# Teensy_board.net
KiCad netlist of a schematic drawn in EAGLE
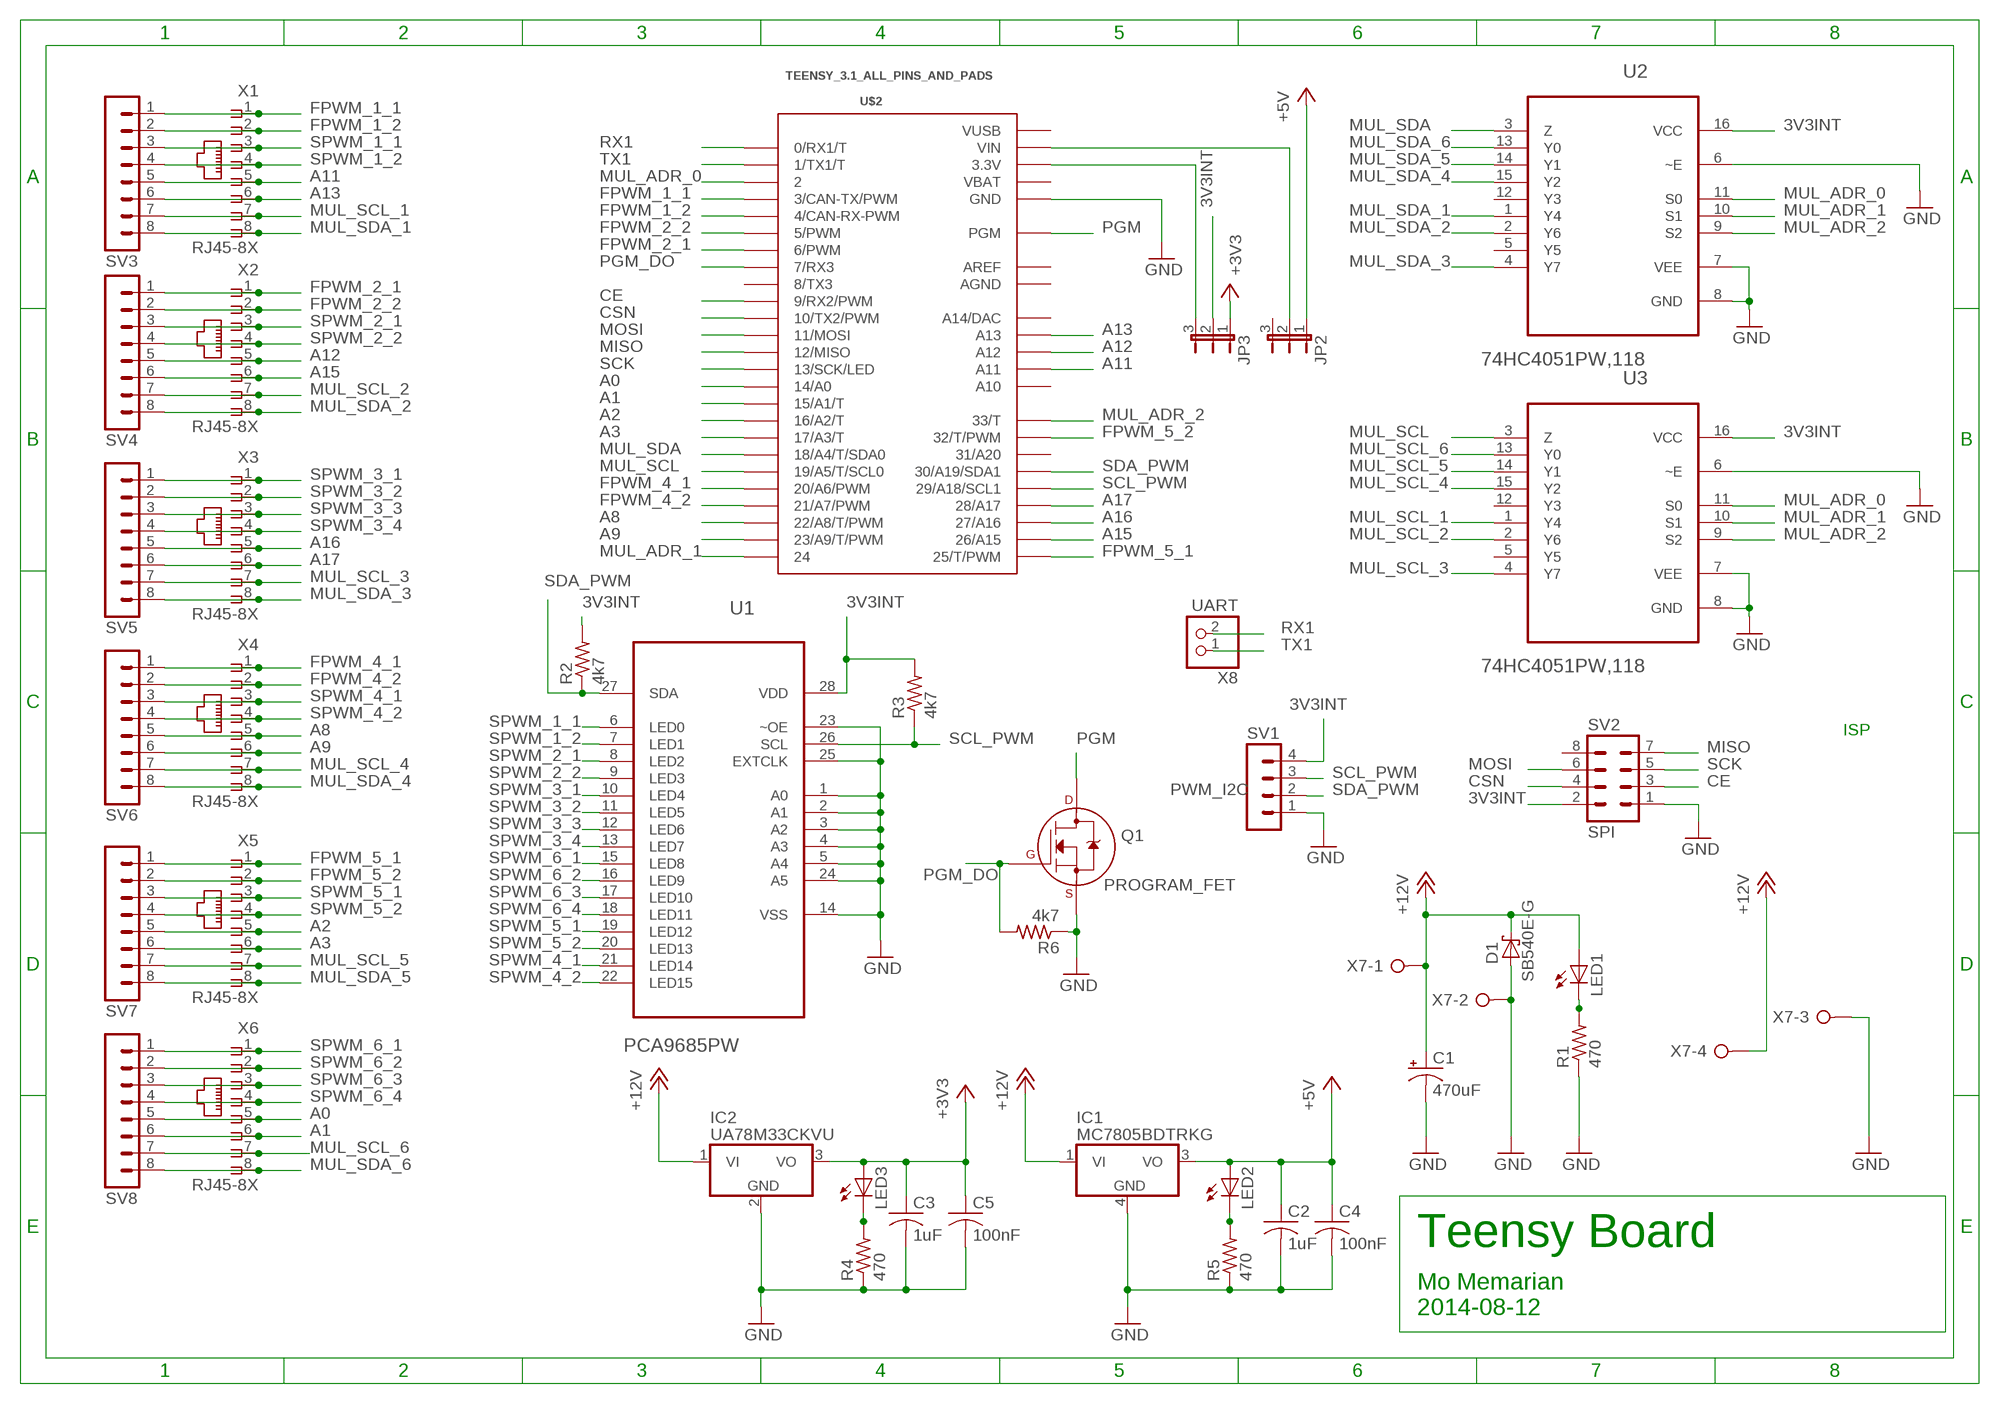
[diagram p0: schematic, sheet 1]

(export (version "E")
  (design (tool "Eeschema 10.0.6"))
  (components
    (comp (ref "C1")
      (value "470uF")
      (footprint "eagle-import:E5-10,5")
      (libsource (lib "eagle-import") (part "CPOL-USE5-10.5"))
    )
    (comp (ref "C2")
      (value "1uF")
      (footprint "eagle-import:C0603")
      (libsource (lib "eagle-import") (part "C-USC0603"))
    )
    (comp (ref "C3")
      (value "1uF")
      (footprint "eagle-import:C0603")
      (libsource (lib "eagle-import") (part "C-USC0603"))
    )
    (comp (ref "C4")
      (value "100nF")
      (footprint "eagle-import:C0603")
      (libsource (lib "eagle-import") (part "C-USC0603"))
    )
    (comp (ref "C5")
      (value "100nF")
      (footprint "eagle-import:C0603")
      (libsource (lib "eagle-import") (part "C-USC0603"))
    )
    (comp (ref "D1")
      (value "SB540E-G")
      (footprint "eagle-import:DO201T15")
      (libsource (lib "eagle-import") (part "SB540E-G"))
    )
    (comp (ref "IC1")
      (value "MC7805BDTRKG")
      (footprint "eagle-import:DPACK_3")
      (libsource (lib "eagle-import") (part "MC7805BDTRKG"))
    )
    (comp (ref "IC2")
      (value "UA78M33CKVU")
      (footprint "eagle-import:DPACK")
      (libsource (lib "eagle-import") (part "UA78MKVU33C"))
    )
    (comp (ref "JP2")
      (value "JP2E")
      (footprint "eagle-import:JP2")
      (libsource (lib "eagle-import") (part "JP2E"))
    )
    (comp (ref "JP3")
      (value "JP2E")
      (footprint "eagle-import:JP2")
      (libsource (lib "eagle-import") (part "JP2E"))
    )
    (comp (ref "LED1")
      (value "LEDSML1206")
      (footprint "eagle-import:SML1206")
      (libsource (lib "eagle-import") (part "LEDSML1206"))
    )
    (comp (ref "LED2")
      (value "LEDSML1206")
      (footprint "eagle-import:SML1206")
      (libsource (lib "eagle-import") (part "LEDSML1206"))
    )
    (comp (ref "LED3")
      (value "LEDSML1206")
      (footprint "eagle-import:SML1206")
      (libsource (lib "eagle-import") (part "LEDSML1206"))
    )
    (comp (ref "Q1")
      (value "PROGRAM_FET")
      (footprint "eagle-import:SOT-23")
      (libsource (lib "eagle-import") (part "2N700_SOT232"))
    )
    (comp (ref "R1")
      (value "470")
      (footprint "eagle-import:R0603")
      (libsource (lib "eagle-import") (part "R-US_R0603"))
    )
    (comp (ref "R2")
      (value "4k7")
      (footprint "eagle-import:R0603")
      (libsource (lib "eagle-import") (part "R-US_R0603"))
    )
    (comp (ref "R3")
      (value "4k7")
      (footprint "eagle-import:R0603")
      (libsource (lib "eagle-import") (part "R-US_R0603"))
    )
    (comp (ref "R4")
      (value "470")
      (footprint "eagle-import:R0603")
      (libsource (lib "eagle-import") (part "R-US_R0603"))
    )
    (comp (ref "R5")
      (value "470")
      (footprint "eagle-import:R0603")
      (libsource (lib "eagle-import") (part "R-US_R0603"))
    )
    (comp (ref "R6")
      (value "4k7")
      (footprint "eagle-import:R0603")
      (libsource (lib "eagle-import") (part "R-US_R0603"))
    )
    (comp (ref "SV1")
      (value "PWM_I2C")
      (footprint "eagle-import:MA04-1")
      (libsource (lib "eagle-import") (part "MA04-1"))
    )
    (comp (ref "SV2")
      (value "SPI")
      (footprint "eagle-import:MA04-2")
      (libsource (lib "eagle-import") (part "MA04-2"))
    )
    (comp (ref "SV3")
      (value "MA08-1")
      (footprint "eagle-import:MA08-1")
      (libsource (lib "eagle-import") (part "MA08-1"))
    )
    (comp (ref "SV4")
      (value "MA08-1")
      (footprint "eagle-import:MA08-1")
      (libsource (lib "eagle-import") (part "MA08-1"))
    )
    (comp (ref "SV5")
      (value "MA08-1")
      (footprint "eagle-import:MA08-1")
      (libsource (lib "eagle-import") (part "MA08-1"))
    )
    (comp (ref "SV6")
      (value "MA08-1")
      (footprint "eagle-import:MA08-1")
      (libsource (lib "eagle-import") (part "MA08-1"))
    )
    (comp (ref "SV7")
      (value "MA08-1")
      (footprint "eagle-import:MA08-1")
      (libsource (lib "eagle-import") (part "MA08-1"))
    )
    (comp (ref "SV8")
      (value "MA08-1")
      (footprint "eagle-import:MA08-1")
      (libsource (lib "eagle-import") (part "MA08-1"))
    )
    (comp (ref "U$2")
      (value "TEENSY_3.1_ALL_PINS_AND_PADS")
      (footprint "eagle-import:TEENSY_3.1_ALLPINS")
      (libsource (lib "eagle-import") (part "TEENSY_3.1_ALL_PINS_AND_PADS"))
    )
    (comp (ref "U1")
      (value "PCA9685PW")
      (footprint "eagle-import:SOP65P640X110-28N")
      (libsource (lib "eagle-import") (part "PCA9685PW"))
    )
    (comp (ref "U2")
      (value "74HC4051PW,118")
      (footprint "eagle-import:SOP65P640X110-16N")
      (libsource (lib "eagle-import") (part "74HC4051PW,118"))
    )
    (comp (ref "U3")
      (value "74HC4051PW,118")
      (footprint "eagle-import:SOP65P640X110-16N")
      (libsource (lib "eagle-import") (part "74HC4051PW,118"))
    )
    (comp (ref "X1")
      (value "RJ45-8X")
      (footprint "eagle-import:RJ45-NO-SHIELD")
      (libsource (lib "eagle-import") (part "RJ45-8X"))
    )
    (comp (ref "X2")
      (value "RJ45-8X")
      (footprint "eagle-import:RJ45-NO-SHIELD")
      (libsource (lib "eagle-import") (part "RJ45-8X"))
    )
    (comp (ref "X3")
      (value "RJ45-8X")
      (footprint "eagle-import:RJ45-NO-SHIELD")
      (libsource (lib "eagle-import") (part "RJ45-8X"))
    )
    (comp (ref "X4")
      (value "RJ45-8X")
      (footprint "eagle-import:RJ45-NO-SHIELD")
      (libsource (lib "eagle-import") (part "RJ45-8X"))
    )
    (comp (ref "X5")
      (value "RJ45-8X")
      (footprint "eagle-import:RJ45-NO-SHIELD")
      (libsource (lib "eagle-import") (part "RJ45-8X"))
    )
    (comp (ref "X6")
      (value "RJ45-8X")
      (footprint "eagle-import:RJ45-NO-SHIELD")
      (libsource (lib "eagle-import") (part "RJ45-8X"))
    )
    (comp (ref "X7")
      (value "W237-04P")
      (footprint "eagle-import:W237-4P")
      (libsource (lib "eagle-import") (part "W237-04P"))
    )
    (comp (ref "X8")
      (value "UART")
      (footprint "eagle-import:1X02")
      (libsource (lib "eagle-import") (part "PINHD-1X2"))
    )
  )
  (nets
    (net (code "1") (name "+3V3") (class "Default")
      (node (ref "C3") (pin "1") (pinfunction "1_1") (pintype "passive"))
      (node (ref "C5") (pin "1") (pinfunction "1_1") (pintype "passive"))
      (node (ref "IC2") (pin "3") (pinfunction "VO_3") (pintype "passive"))
      (node (ref "JP3") (pin "1") (pinfunction "1_1") (pintype "passive"))
      (node (ref "LED3") (pin "A") (pinfunction "A_A") (pintype "passive"))
    )
    (net (code "2") (name "+5V") (class "Default")
      (node (ref "C2") (pin "1") (pinfunction "1_1") (pintype "passive"))
      (node (ref "C4") (pin "1") (pinfunction "1_1") (pintype "passive"))
      (node (ref "IC1") (pin "3") (pinfunction "VO_3") (pintype "passive"))
      (node (ref "JP2") (pin "1") (pinfunction "1_1") (pintype "passive"))
      (node (ref "LED2") (pin "A") (pinfunction "A_A") (pintype "passive"))
    )
    (net (code "3") (name "+12V") (class "Default")
      (node (ref "C1") (pin "+") (pinfunction "+_+") (pintype "passive"))
      (node (ref "D1") (pin "C") (pinfunction "C_C") (pintype "passive"))
      (node (ref "IC1") (pin "1") (pinfunction "VI_1") (pintype "input"))
      (node (ref "IC2") (pin "1") (pinfunction "VI_1") (pintype "input"))
      (node (ref "LED1") (pin "A") (pinfunction "A_A") (pintype "passive"))
      (node (ref "X7") (pin "1") (pinfunction "KL_1") (pintype "passive"))
      (node (ref "X7") (pin "4") (pinfunction "KL_4") (pintype "passive"))
    )
    (net (code "4") (name "/3V3INT") (class "Default")
      (node (ref "JP3") (pin "2") (pinfunction "2_2") (pintype "passive"))
      (node (ref "R2") (pin "2") (pinfunction "2_2") (pintype "passive"))
      (node (ref "R3") (pin "2") (pinfunction "2_2") (pintype "passive"))
      (node (ref "SV1") (pin "4") (pinfunction "4_4") (pintype "passive"))
      (node (ref "SV2") (pin "2") (pinfunction "2_2") (pintype "passive"))
      (node (ref "U1") (pin "28") (pinfunction "VDD_28") (pintype "power_in"))
      (node (ref "U2") (pin "16") (pinfunction "VCC_16") (pintype "power_in"))
      (node (ref "U3") (pin "16") (pinfunction "VCC_16") (pintype "power_in"))
    )
    (net (code "5") (name "/A0") (class "Default")
      (node (ref "SV8") (pin "5") (pinfunction "5_5") (pintype "passive"))
      (node (ref "U$2") (pin "14/A0") (pinfunction "14/A0_14/A0") (pintype "bidirectional"))
      (node (ref "X6") (pin "5") (pinfunction "5_5") (pintype "passive"))
    )
    (net (code "6") (name "/A1") (class "Default")
      (node (ref "SV8") (pin "6") (pinfunction "6_6") (pintype "passive"))
      (node (ref "U$2") (pin "15/A1") (pinfunction "15/A1/T_15/A1") (pintype "bidirectional"))
      (node (ref "X6") (pin "6") (pinfunction "6_6") (pintype "passive"))
    )
    (net (code "7") (name "/A2") (class "Default")
      (node (ref "SV7") (pin "5") (pinfunction "5_5") (pintype "passive"))
      (node (ref "U$2") (pin "16/A2") (pinfunction "16/A2/T_16/A2") (pintype "bidirectional"))
      (node (ref "X5") (pin "5") (pinfunction "5_5") (pintype "passive"))
    )
    (net (code "8") (name "/A3") (class "Default")
      (node (ref "SV7") (pin "6") (pinfunction "6_6") (pintype "passive"))
      (node (ref "U$2") (pin "17/A3") (pinfunction "17/A3/T_17/A3") (pintype "bidirectional"))
      (node (ref "X5") (pin "6") (pinfunction "6_6") (pintype "passive"))
    )
    (net (code "9") (name "/A8") (class "Default")
      (node (ref "SV6") (pin "5") (pinfunction "5_5") (pintype "passive"))
      (node (ref "U$2") (pin "22/A8") (pinfunction "22/A8/T/PWM_22/A8") (pintype "bidirectional"))
      (node (ref "X4") (pin "5") (pinfunction "5_5") (pintype "passive"))
    )
    (net (code "10") (name "/A9") (class "Default")
      (node (ref "SV6") (pin "6") (pinfunction "6_6") (pintype "passive"))
      (node (ref "U$2") (pin "23/A9") (pinfunction "23/A9/T/PWM_23/A9") (pintype "bidirectional"))
      (node (ref "X4") (pin "6") (pinfunction "6_6") (pintype "passive"))
    )
    (net (code "11") (name "/A11") (class "Default")
      (node (ref "SV3") (pin "5") (pinfunction "5_5") (pintype "passive"))
      (node (ref "U$2") (pin "A11") (pinfunction "A11_A11") (pintype "bidirectional"))
      (node (ref "X1") (pin "5") (pinfunction "5_5") (pintype "passive"))
    )
    (net (code "12") (name "/A12") (class "Default")
      (node (ref "SV4") (pin "5") (pinfunction "5_5") (pintype "passive"))
      (node (ref "U$2") (pin "A12") (pinfunction "A12_A12") (pintype "bidirectional"))
      (node (ref "X2") (pin "5") (pinfunction "5_5") (pintype "passive"))
    )
    (net (code "13") (name "/A13") (class "Default")
      (node (ref "SV3") (pin "6") (pinfunction "6_6") (pintype "passive"))
      (node (ref "U$2") (pin "A13") (pinfunction "A13_A13") (pintype "bidirectional"))
      (node (ref "X1") (pin "6") (pinfunction "6_6") (pintype "passive"))
    )
    (net (code "14") (name "/A15") (class "Default")
      (node (ref "SV4") (pin "6") (pinfunction "6_6") (pintype "passive"))
      (node (ref "U$2") (pin "26") (pinfunction "26/A15_26") (pintype "bidirectional"))
      (node (ref "X2") (pin "6") (pinfunction "6_6") (pintype "passive"))
    )
    (net (code "15") (name "/A16") (class "Default")
      (node (ref "SV5") (pin "5") (pinfunction "5_5") (pintype "passive"))
      (node (ref "U$2") (pin "27") (pinfunction "27/A16_27") (pintype "bidirectional"))
      (node (ref "X3") (pin "5") (pinfunction "5_5") (pintype "passive"))
    )
    (net (code "16") (name "/A17") (class "Default")
      (node (ref "SV5") (pin "6") (pinfunction "6_6") (pintype "passive"))
      (node (ref "U$2") (pin "28") (pinfunction "28/A17_28") (pintype "bidirectional"))
      (node (ref "X3") (pin "6") (pinfunction "6_6") (pintype "passive"))
    )
    (net (code "17") (name "/AGND") (class "Default")
      (node (ref "U$2") (pin "AGND") (pinfunction "AGND_AGND") (pintype "power_in"))
    )
    (net (code "18") (name "/AREF") (class "Default")
      (node (ref "U$2") (pin "AREF") (pinfunction "AREF_AREF") (pintype "power_in"))
    )
    (net (code "19") (name "/CE") (class "Default")
      (node (ref "SV2") (pin "3") (pinfunction "3_3") (pintype "passive"))
      (node (ref "U$2") (pin "9") (pinfunction "9/RX2/PWM_9") (pintype "bidirectional"))
    )
    (net (code "20") (name "/CSN") (class "Default")
      (node (ref "SV2") (pin "4") (pinfunction "4_4") (pintype "passive"))
      (node (ref "U$2") (pin "10") (pinfunction "10/TX2/PWM_10") (pintype "bidirectional"))
    )
    (net (code "21") (name "/FPWM_1_1") (class "Default")
      (node (ref "SV3") (pin "1") (pinfunction "1_1") (pintype "passive"))
      (node (ref "U$2") (pin "3") (pinfunction "3/CAN-TX/PWM_3") (pintype "bidirectional"))
      (node (ref "X1") (pin "1") (pinfunction "1_1") (pintype "passive"))
    )
    (net (code "22") (name "/FPWM_1_2") (class "Default")
      (node (ref "SV3") (pin "2") (pinfunction "2_2") (pintype "passive"))
      (node (ref "U$2") (pin "4") (pinfunction "4/CAN-RX-PWM_4") (pintype "bidirectional"))
      (node (ref "X1") (pin "2") (pinfunction "2_2") (pintype "passive"))
    )
    (net (code "23") (name "/FPWM_2_1") (class "Default")
      (node (ref "SV4") (pin "1") (pinfunction "1_1") (pintype "passive"))
      (node (ref "U$2") (pin "6") (pinfunction "6/PWM_6") (pintype "bidirectional"))
      (node (ref "X2") (pin "1") (pinfunction "1_1") (pintype "passive"))
    )
    (net (code "24") (name "/FPWM_2_2") (class "Default")
      (node (ref "SV4") (pin "2") (pinfunction "2_2") (pintype "passive"))
      (node (ref "U$2") (pin "5") (pinfunction "5/PWM_5") (pintype "bidirectional"))
      (node (ref "X2") (pin "2") (pinfunction "2_2") (pintype "passive"))
    )
    (net (code "25") (name "/FPWM_4_1") (class "Default")
      (node (ref "SV6") (pin "1") (pinfunction "1_1") (pintype "passive"))
      (node (ref "U$2") (pin "20/A6") (pinfunction "20/A6/PWM_20/A6") (pintype "bidirectional"))
      (node (ref "X4") (pin "1") (pinfunction "1_1") (pintype "passive"))
    )
    (net (code "26") (name "/FPWM_4_2") (class "Default")
      (node (ref "SV6") (pin "2") (pinfunction "2_2") (pintype "passive"))
      (node (ref "U$2") (pin "21/A7") (pinfunction "21/A7/PWM_21/A7") (pintype "bidirectional"))
      (node (ref "X4") (pin "2") (pinfunction "2_2") (pintype "passive"))
    )
    (net (code "27") (name "/FPWM_5_1") (class "Default")
      (node (ref "SV7") (pin "1") (pinfunction "1_1") (pintype "passive"))
      (node (ref "U$2") (pin "25") (pinfunction "25/T/PWM_25") (pintype "bidirectional"))
      (node (ref "X5") (pin "1") (pinfunction "1_1") (pintype "passive"))
    )
    (net (code "28") (name "/FPWM_5_2") (class "Default")
      (node (ref "SV7") (pin "2") (pinfunction "2_2") (pintype "passive"))
      (node (ref "U$2") (pin "32") (pinfunction "32/T/PWM_32") (pintype "bidirectional"))
      (node (ref "X5") (pin "2") (pinfunction "2_2") (pintype "passive"))
    )
    (net (code "29") (name "/MISO") (class "Default")
      (node (ref "SV2") (pin "7") (pinfunction "7_7") (pintype "passive"))
      (node (ref "U$2") (pin "12") (pinfunction "12/MISO_12") (pintype "bidirectional"))
    )
    (net (code "30") (name "/MOSI") (class "Default")
      (node (ref "SV2") (pin "6") (pinfunction "6_6") (pintype "passive"))
      (node (ref "U$2") (pin "11") (pinfunction "11/MOSI_11") (pintype "bidirectional"))
    )
    (net (code "31") (name "/MUL_ADR_0") (class "Default")
      (node (ref "U$2") (pin "2") (pinfunction "2_2") (pintype "bidirectional"))
      (node (ref "U2") (pin "11") (pinfunction "S0_11") (pintype "input"))
      (node (ref "U3") (pin "11") (pinfunction "S0_11") (pintype "input"))
    )
    (net (code "32") (name "/MUL_ADR_1") (class "Default")
      (node (ref "U$2") (pin "24") (pinfunction "24_24") (pintype "bidirectional"))
      (node (ref "U2") (pin "10") (pinfunction "S1_10") (pintype "input"))
      (node (ref "U3") (pin "10") (pinfunction "S1_10") (pintype "input"))
    )
    (net (code "33") (name "/MUL_ADR_2") (class "Default")
      (node (ref "U$2") (pin "33") (pinfunction "33/T_33") (pintype "bidirectional"))
      (node (ref "U2") (pin "9") (pinfunction "S2_9") (pintype "input"))
      (node (ref "U3") (pin "9") (pinfunction "S2_9") (pintype "input"))
    )
    (net (code "34") (name "/MUL_SCL") (class "Default")
      (node (ref "U$2") (pin "19/A5") (pinfunction "19/A5/T/SCL0_19/A5") (pintype "bidirectional"))
      (node (ref "U3") (pin "3") (pinfunction "Z_3") (pintype "bidirectional"))
    )
    (net (code "35") (name "/MUL_SCL_1") (class "Default")
      (node (ref "SV3") (pin "7") (pinfunction "7_7") (pintype "passive"))
      (node (ref "U3") (pin "1") (pinfunction "Y4_1") (pintype "bidirectional"))
      (node (ref "X1") (pin "7") (pinfunction "7_7") (pintype "passive"))
    )
    (net (code "36") (name "/MUL_SCL_2") (class "Default")
      (node (ref "SV4") (pin "7") (pinfunction "7_7") (pintype "passive"))
      (node (ref "U3") (pin "2") (pinfunction "Y6_2") (pintype "bidirectional"))
      (node (ref "X2") (pin "7") (pinfunction "7_7") (pintype "passive"))
    )
    (net (code "37") (name "/MUL_SCL_3") (class "Default")
      (node (ref "SV5") (pin "7") (pinfunction "7_7") (pintype "passive"))
      (node (ref "U3") (pin "4") (pinfunction "Y7_4") (pintype "bidirectional"))
      (node (ref "X3") (pin "7") (pinfunction "7_7") (pintype "passive"))
    )
    (net (code "38") (name "/MUL_SCL_4") (class "Default")
      (node (ref "SV6") (pin "7") (pinfunction "7_7") (pintype "passive"))
      (node (ref "U3") (pin "15") (pinfunction "Y2_15") (pintype "bidirectional"))
      (node (ref "X4") (pin "7") (pinfunction "7_7") (pintype "passive"))
    )
    (net (code "39") (name "/MUL_SCL_5") (class "Default")
      (node (ref "SV7") (pin "7") (pinfunction "7_7") (pintype "passive"))
      (node (ref "U3") (pin "14") (pinfunction "Y1_14") (pintype "bidirectional"))
      (node (ref "X5") (pin "7") (pinfunction "7_7") (pintype "passive"))
    )
    (net (code "40") (name "/MUL_SCL_6") (class "Default")
      (node (ref "SV8") (pin "7") (pinfunction "7_7") (pintype "passive"))
      (node (ref "U3") (pin "13") (pinfunction "Y0_13") (pintype "bidirectional"))
      (node (ref "X6") (pin "7") (pinfunction "7_7") (pintype "passive"))
    )
    (net (code "41") (name "/MUL_SDA") (class "Default")
      (node (ref "U$2") (pin "18/A4") (pinfunction "18/A4/T/SDA0_18/A4") (pintype "bidirectional"))
      (node (ref "U2") (pin "3") (pinfunction "Z_3") (pintype "bidirectional"))
    )
    (net (code "42") (name "/MUL_SDA_1") (class "Default")
      (node (ref "SV3") (pin "8") (pinfunction "8_8") (pintype "passive"))
      (node (ref "U2") (pin "1") (pinfunction "Y4_1") (pintype "bidirectional"))
      (node (ref "X1") (pin "8") (pinfunction "8_8") (pintype "passive"))
    )
    (net (code "43") (name "/MUL_SDA_2") (class "Default")
      (node (ref "SV4") (pin "8") (pinfunction "8_8") (pintype "passive"))
      (node (ref "U2") (pin "2") (pinfunction "Y6_2") (pintype "bidirectional"))
      (node (ref "X2") (pin "8") (pinfunction "8_8") (pintype "passive"))
    )
    (net (code "44") (name "/MUL_SDA_3") (class "Default")
      (node (ref "SV5") (pin "8") (pinfunction "8_8") (pintype "passive"))
      (node (ref "U2") (pin "4") (pinfunction "Y7_4") (pintype "bidirectional"))
      (node (ref "X3") (pin "8") (pinfunction "8_8") (pintype "passive"))
    )
    (net (code "45") (name "/MUL_SDA_4") (class "Default")
      (node (ref "SV6") (pin "8") (pinfunction "8_8") (pintype "passive"))
      (node (ref "U2") (pin "15") (pinfunction "Y2_15") (pintype "bidirectional"))
      (node (ref "X4") (pin "8") (pinfunction "8_8") (pintype "passive"))
    )
    (net (code "46") (name "/MUL_SDA_5") (class "Default")
      (node (ref "SV7") (pin "8") (pinfunction "8_8") (pintype "passive"))
      (node (ref "U2") (pin "14") (pinfunction "Y1_14") (pintype "bidirectional"))
      (node (ref "X5") (pin "8") (pinfunction "8_8") (pintype "passive"))
    )
    (net (code "47") (name "/MUL_SDA_6") (class "Default")
      (node (ref "SV8") (pin "8") (pinfunction "8_8") (pintype "passive"))
      (node (ref "U2") (pin "13") (pinfunction "Y0_13") (pintype "bidirectional"))
      (node (ref "X6") (pin "8") (pinfunction "8_8") (pintype "passive"))
    )
    (net (code "48") (name "/PGM") (class "Default")
      (node (ref "Q1") (pin "3") (pinfunction "D_3") (pintype "bidirectional"))
      (node (ref "U$2") (pin "PGM") (pinfunction "PGM_PGM") (pintype "bidirectional"))
    )
    (net (code "49") (name "/PGM_DO") (class "Default")
      (node (ref "Q1") (pin "1") (pinfunction "G_1") (pintype "tri_state"))
      (node (ref "R6") (pin "2") (pinfunction "2_2") (pintype "passive"))
      (node (ref "U$2") (pin "7") (pinfunction "7/RX3_7") (pintype "bidirectional"))
    )
    (net (code "50") (name "/RX1") (class "Default")
      (node (ref "U$2") (pin "0") (pinfunction "0/RX1/T_0") (pintype "bidirectional"))
      (node (ref "X8") (pin "2") (pinfunction "2_2") (pintype "passive"))
    )
    (net (code "51") (name "/SCK") (class "Default")
      (node (ref "SV2") (pin "5") (pinfunction "5_5") (pintype "passive"))
      (node (ref "U$2") (pin "13") (pinfunction "13/SCK/LED_13") (pintype "bidirectional"))
    )
    (net (code "52") (name "/SCL_PWM") (class "Default")
      (node (ref "R3") (pin "1") (pinfunction "1_1") (pintype "passive"))
      (node (ref "SV1") (pin "3") (pinfunction "3_3") (pintype "passive"))
      (node (ref "U$2") (pin "29") (pinfunction "29/A18/SCL1_29") (pintype "bidirectional"))
      (node (ref "U1") (pin "26") (pinfunction "SCL_26") (pintype "input"))
    )
    (net (code "53") (name "/SDA_PWM") (class "Default")
      (node (ref "R2") (pin "1") (pinfunction "1_1") (pintype "passive"))
      (node (ref "SV1") (pin "2") (pinfunction "2_2") (pintype "passive"))
      (node (ref "U$2") (pin "30") (pinfunction "30/A19/SDA1_30") (pintype "bidirectional"))
      (node (ref "U1") (pin "27") (pinfunction "SDA_27") (pintype "bidirectional"))
    )
    (net (code "54") (name "/SPWM_1_1") (class "Default")
      (node (ref "SV3") (pin "3") (pinfunction "3_3") (pintype "passive"))
      (node (ref "U1") (pin "6") (pinfunction "LED0_6") (pintype "output"))
      (node (ref "X1") (pin "3") (pinfunction "3_3") (pintype "passive"))
    )
    (net (code "55") (name "/SPWM_1_2") (class "Default")
      (node (ref "SV3") (pin "4") (pinfunction "4_4") (pintype "passive"))
      (node (ref "U1") (pin "7") (pinfunction "LED1_7") (pintype "output"))
      (node (ref "X1") (pin "4") (pinfunction "4_4") (pintype "passive"))
    )
    (net (code "56") (name "/SPWM_2_1") (class "Default")
      (node (ref "SV4") (pin "3") (pinfunction "3_3") (pintype "passive"))
      (node (ref "U1") (pin "8") (pinfunction "LED2_8") (pintype "output"))
      (node (ref "X2") (pin "3") (pinfunction "3_3") (pintype "passive"))
    )
    (net (code "57") (name "/SPWM_2_2") (class "Default")
      (node (ref "SV4") (pin "4") (pinfunction "4_4") (pintype "passive"))
      (node (ref "U1") (pin "9") (pinfunction "LED3_9") (pintype "output"))
      (node (ref "X2") (pin "4") (pinfunction "4_4") (pintype "passive"))
    )
    (net (code "58") (name "/SPWM_3_1") (class "Default")
      (node (ref "SV5") (pin "1") (pinfunction "1_1") (pintype "passive"))
      (node (ref "U1") (pin "10") (pinfunction "LED4_10") (pintype "output"))
      (node (ref "X3") (pin "1") (pinfunction "1_1") (pintype "passive"))
    )
    (net (code "59") (name "/SPWM_3_2") (class "Default")
      (node (ref "SV5") (pin "2") (pinfunction "2_2") (pintype "passive"))
      (node (ref "U1") (pin "11") (pinfunction "LED5_11") (pintype "output"))
      (node (ref "X3") (pin "2") (pinfunction "2_2") (pintype "passive"))
    )
    (net (code "60") (name "/SPWM_3_3") (class "Default")
      (node (ref "SV5") (pin "3") (pinfunction "3_3") (pintype "passive"))
      (node (ref "U1") (pin "12") (pinfunction "LED6_12") (pintype "output"))
      (node (ref "X3") (pin "3") (pinfunction "3_3") (pintype "passive"))
    )
    (net (code "61") (name "/SPWM_3_4") (class "Default")
      (node (ref "SV5") (pin "4") (pinfunction "4_4") (pintype "passive"))
      (node (ref "U1") (pin "13") (pinfunction "LED7_13") (pintype "output"))
      (node (ref "X3") (pin "4") (pinfunction "4_4") (pintype "passive"))
    )
    (net (code "62") (name "/SPWM_4_1") (class "Default")
      (node (ref "SV6") (pin "3") (pinfunction "3_3") (pintype "passive"))
      (node (ref "U1") (pin "21") (pinfunction "LED14_21") (pintype "output"))
      (node (ref "X4") (pin "3") (pinfunction "3_3") (pintype "passive"))
    )
    (net (code "63") (name "/SPWM_4_2") (class "Default")
      (node (ref "SV6") (pin "4") (pinfunction "4_4") (pintype "passive"))
      (node (ref "U1") (pin "22") (pinfunction "LED15_22") (pintype "output"))
      (node (ref "X4") (pin "4") (pinfunction "4_4") (pintype "passive"))
    )
    (net (code "64") (name "/SPWM_5_1") (class "Default")
      (node (ref "SV7") (pin "3") (pinfunction "3_3") (pintype "passive"))
      (node (ref "U1") (pin "19") (pinfunction "LED12_19") (pintype "output"))
      (node (ref "X5") (pin "3") (pinfunction "3_3") (pintype "passive"))
    )
    (net (code "65") (name "/SPWM_5_2") (class "Default")
      (node (ref "SV7") (pin "4") (pinfunction "4_4") (pintype "passive"))
      (node (ref "U1") (pin "20") (pinfunction "LED13_20") (pintype "output"))
      (node (ref "X5") (pin "4") (pinfunction "4_4") (pintype "passive"))
    )
    (net (code "66") (name "/SPWM_6_1") (class "Default")
      (node (ref "SV8") (pin "1") (pinfunction "1_1") (pintype "passive"))
      (node (ref "U1") (pin "15") (pinfunction "LED8_15") (pintype "output"))
      (node (ref "X6") (pin "1") (pinfunction "1_1") (pintype "passive"))
    )
    (net (code "67") (name "/SPWM_6_2") (class "Default")
      (node (ref "SV8") (pin "2") (pinfunction "2_2") (pintype "passive"))
      (node (ref "U1") (pin "16") (pinfunction "LED9_16") (pintype "output"))
      (node (ref "X6") (pin "2") (pinfunction "2_2") (pintype "passive"))
    )
    (net (code "68") (name "/SPWM_6_3") (class "Default")
      (node (ref "SV8") (pin "3") (pinfunction "3_3") (pintype "passive"))
      (node (ref "U1") (pin "17") (pinfunction "LED10_17") (pintype "output"))
      (node (ref "X6") (pin "3") (pinfunction "3_3") (pintype "passive"))
    )
    (net (code "69") (name "/SPWM_6_4") (class "Default")
      (node (ref "SV8") (pin "4") (pinfunction "4_4") (pintype "passive"))
      (node (ref "U1") (pin "18") (pinfunction "LED11_18") (pintype "output"))
      (node (ref "X6") (pin "4") (pinfunction "4_4") (pintype "passive"))
    )
    (net (code "70") (name "/TX1") (class "Default")
      (node (ref "U$2") (pin "1") (pinfunction "1/TX1/T_1") (pintype "bidirectional"))
      (node (ref "X8") (pin "1") (pinfunction "1_1") (pintype "passive"))
    )
    (net (code "71") (name "/VBAT") (class "Default")
      (node (ref "U$2") (pin "VBAT") (pinfunction "VBAT_VBAT") (pintype "power_in"))
    )
    (net (code "72") (name "/VUSB") (class "Default")
      (node (ref "U$2") (pin "VUSB") (pinfunction "VUSB_VUSB") (pintype "power_in"))
    )
    (net (code "73") (name "GND") (class "Default")
      (node (ref "C1") (pin "-") (pinfunction "-_-") (pintype "passive"))
      (node (ref "C2") (pin "2") (pinfunction "2_2") (pintype "passive"))
      (node (ref "C3") (pin "2") (pinfunction "2_2") (pintype "passive"))
      (node (ref "C4") (pin "2") (pinfunction "2_2") (pintype "passive"))
      (node (ref "C5") (pin "2") (pinfunction "2_2") (pintype "passive"))
      (node (ref "D1") (pin "A") (pinfunction "A_A") (pintype "passive"))
      (node (ref "IC1") (pin "4") (pinfunction "GND_4") (pintype "passive"))
      (node (ref "IC2") (pin "2") (pinfunction "GND_2") (pintype "passive"))
      (node (ref "Q1") (pin "2") (pinfunction "S_2") (pintype "bidirectional"))
      (node (ref "R1") (pin "1") (pinfunction "1_1") (pintype "passive"))
      (node (ref "R4") (pin "1") (pinfunction "1_1") (pintype "passive"))
      (node (ref "R5") (pin "1") (pinfunction "1_1") (pintype "passive"))
      (node (ref "R6") (pin "1") (pinfunction "1_1") (pintype "passive"))
      (node (ref "SV1") (pin "1") (pinfunction "1_1") (pintype "passive"))
      (node (ref "SV2") (pin "1") (pinfunction "1_1") (pintype "passive"))
      (node (ref "U$2") (pin "GND") (pinfunction "GND_GND") (pintype "power_in"))
      (node (ref "U$2") (pin "GND1") (pinfunction "GND_GND1") (pintype "power_in"))
      (node (ref "U$2") (pin "GND2") (pinfunction "GND_GND2") (pintype "power_in"))
      (node (ref "U1") (pin "1") (pinfunction "A0_1") (pintype "input"))
      (node (ref "U1") (pin "14") (pinfunction "VSS_14") (pintype "passive"))
      (node (ref "U1") (pin "2") (pinfunction "A1_2") (pintype "input"))
      (node (ref "U1") (pin "23") (pinfunction "~{OE}_23") (pintype "input"))
      (node (ref "U1") (pin "24") (pinfunction "A5_24") (pintype "input"))
      (node (ref "U1") (pin "25") (pinfunction "EXTCLK_25") (pintype "input"))
      (node (ref "U1") (pin "3") (pinfunction "A2_3") (pintype "input"))
      (node (ref "U1") (pin "4") (pinfunction "A3_4") (pintype "input"))
      (node (ref "U1") (pin "5") (pinfunction "A4_5") (pintype "input"))
      (node (ref "U2") (pin "6") (pinfunction "~{E}_6") (pintype "input"))
      (node (ref "U2") (pin "7") (pinfunction "VEE_7") (pintype "power_in"))
      (node (ref "U2") (pin "8") (pinfunction "GND_8") (pintype "passive"))
      (node (ref "U3") (pin "6") (pinfunction "~{E}_6") (pintype "input"))
      (node (ref "U3") (pin "7") (pinfunction "VEE_7") (pintype "power_in"))
      (node (ref "U3") (pin "8") (pinfunction "GND_8") (pintype "passive"))
      (node (ref "X7") (pin "2") (pinfunction "KL_2") (pintype "passive"))
      (node (ref "X7") (pin "3") (pinfunction "KL_3") (pintype "passive"))
    )
    (net (code "74") (name "Net-(JP2-Pad2)") (class "Default")
      (node (ref "JP2") (pin "2") (pinfunction "2_2") (pintype "passive"))
      (node (ref "U$2") (pin "VIN") (pinfunction "VIN_VIN") (pintype "power_in"))
    )
    (net (code "75") (name "Net-(JP3-Pad3)") (class "Default")
      (node (ref "JP3") (pin "3") (pinfunction "3_3") (pintype "passive"))
      (node (ref "U$2") (pin "3.3V") (pinfunction "3.3V_3.3V") (pintype "power_in"))
      (node (ref "U$2") (pin "3.3V1") (pinfunction "3.3V_3.3V1") (pintype "power_in"))
      (node (ref "U$2") (pin "3.3V2") (pinfunction "3.3V_3.3V2") (pintype "power_in"))
    )
    (net (code "76") (name "Net-(LED1-PadC)") (class "Default")
      (node (ref "LED1") (pin "C") (pinfunction "C_C") (pintype "passive"))
      (node (ref "R1") (pin "2") (pinfunction "2_2") (pintype "passive"))
    )
    (net (code "77") (name "Net-(LED2-PadC)") (class "Default")
      (node (ref "LED2") (pin "C") (pinfunction "C_C") (pintype "passive"))
      (node (ref "R5") (pin "2") (pinfunction "2_2") (pintype "passive"))
    )
    (net (code "78") (name "Net-(LED3-PadC)") (class "Default")
      (node (ref "LED3") (pin "C") (pinfunction "C_C") (pintype "passive"))
      (node (ref "R4") (pin "2") (pinfunction "2_2") (pintype "passive"))
    )
    (net (code "79") (name "unconnected-(JP2-Pad3)") (class "Default")
      (node (ref "JP2") (pin "3") (pinfunction "3_3") (pintype "passive"))
    )
    (net (code "80") (name "unconnected-(SV2-Pad8)") (class "Default")
      (node (ref "SV2") (pin "8") (pinfunction "8_8") (pintype "passive"))
    )
    (net (code "81") (name "unconnected-(U$2-8{slash}TX3-Pad8)") (class "Default")
      (node (ref "U$2") (pin "8") (pinfunction "8/TX3_8") (pintype "bidirectional"))
    )
    (net (code "82") (name "unconnected-(U$2-31{slash}A20-Pad31)") (class "Default")
      (node (ref "U$2") (pin "31") (pinfunction "31/A20_31") (pintype "bidirectional"))
    )
    (net (code "83") (name "unconnected-(U$2-A14{slash}DAC-PadA14)") (class "Default")
      (node (ref "U$2") (pin "A14") (pinfunction "A14/DAC_A14") (pintype "bidirectional"))
    )
    (net (code "84") (name "unconnected-(U$2-PadA10)") (class "Default")
      (node (ref "U$2") (pin "A10") (pinfunction "A10_A10") (pintype "bidirectional"))
    )
    (net (code "85") (name "unconnected-(U2-Y3-Pad12)") (class "Default")
      (node (ref "U2") (pin "12") (pinfunction "Y3_12") (pintype "bidirectional"))
    )
    (net (code "86") (name "unconnected-(U2-Y5-Pad5)") (class "Default")
      (node (ref "U2") (pin "5") (pinfunction "Y5_5") (pintype "bidirectional"))
    )
    (net (code "87") (name "unconnected-(U3-Y3-Pad12)") (class "Default")
      (node (ref "U3") (pin "12") (pinfunction "Y3_12") (pintype "bidirectional"))
    )
    (net (code "88") (name "unconnected-(U3-Y5-Pad5)") (class "Default")
      (node (ref "U3") (pin "5") (pinfunction "Y5_5") (pintype "bidirectional"))
    )
  )
)
